# rapidshark-main-breakout-top-teensy-mk-1.net
KiCad netlist of a schematic drawn in EAGLE
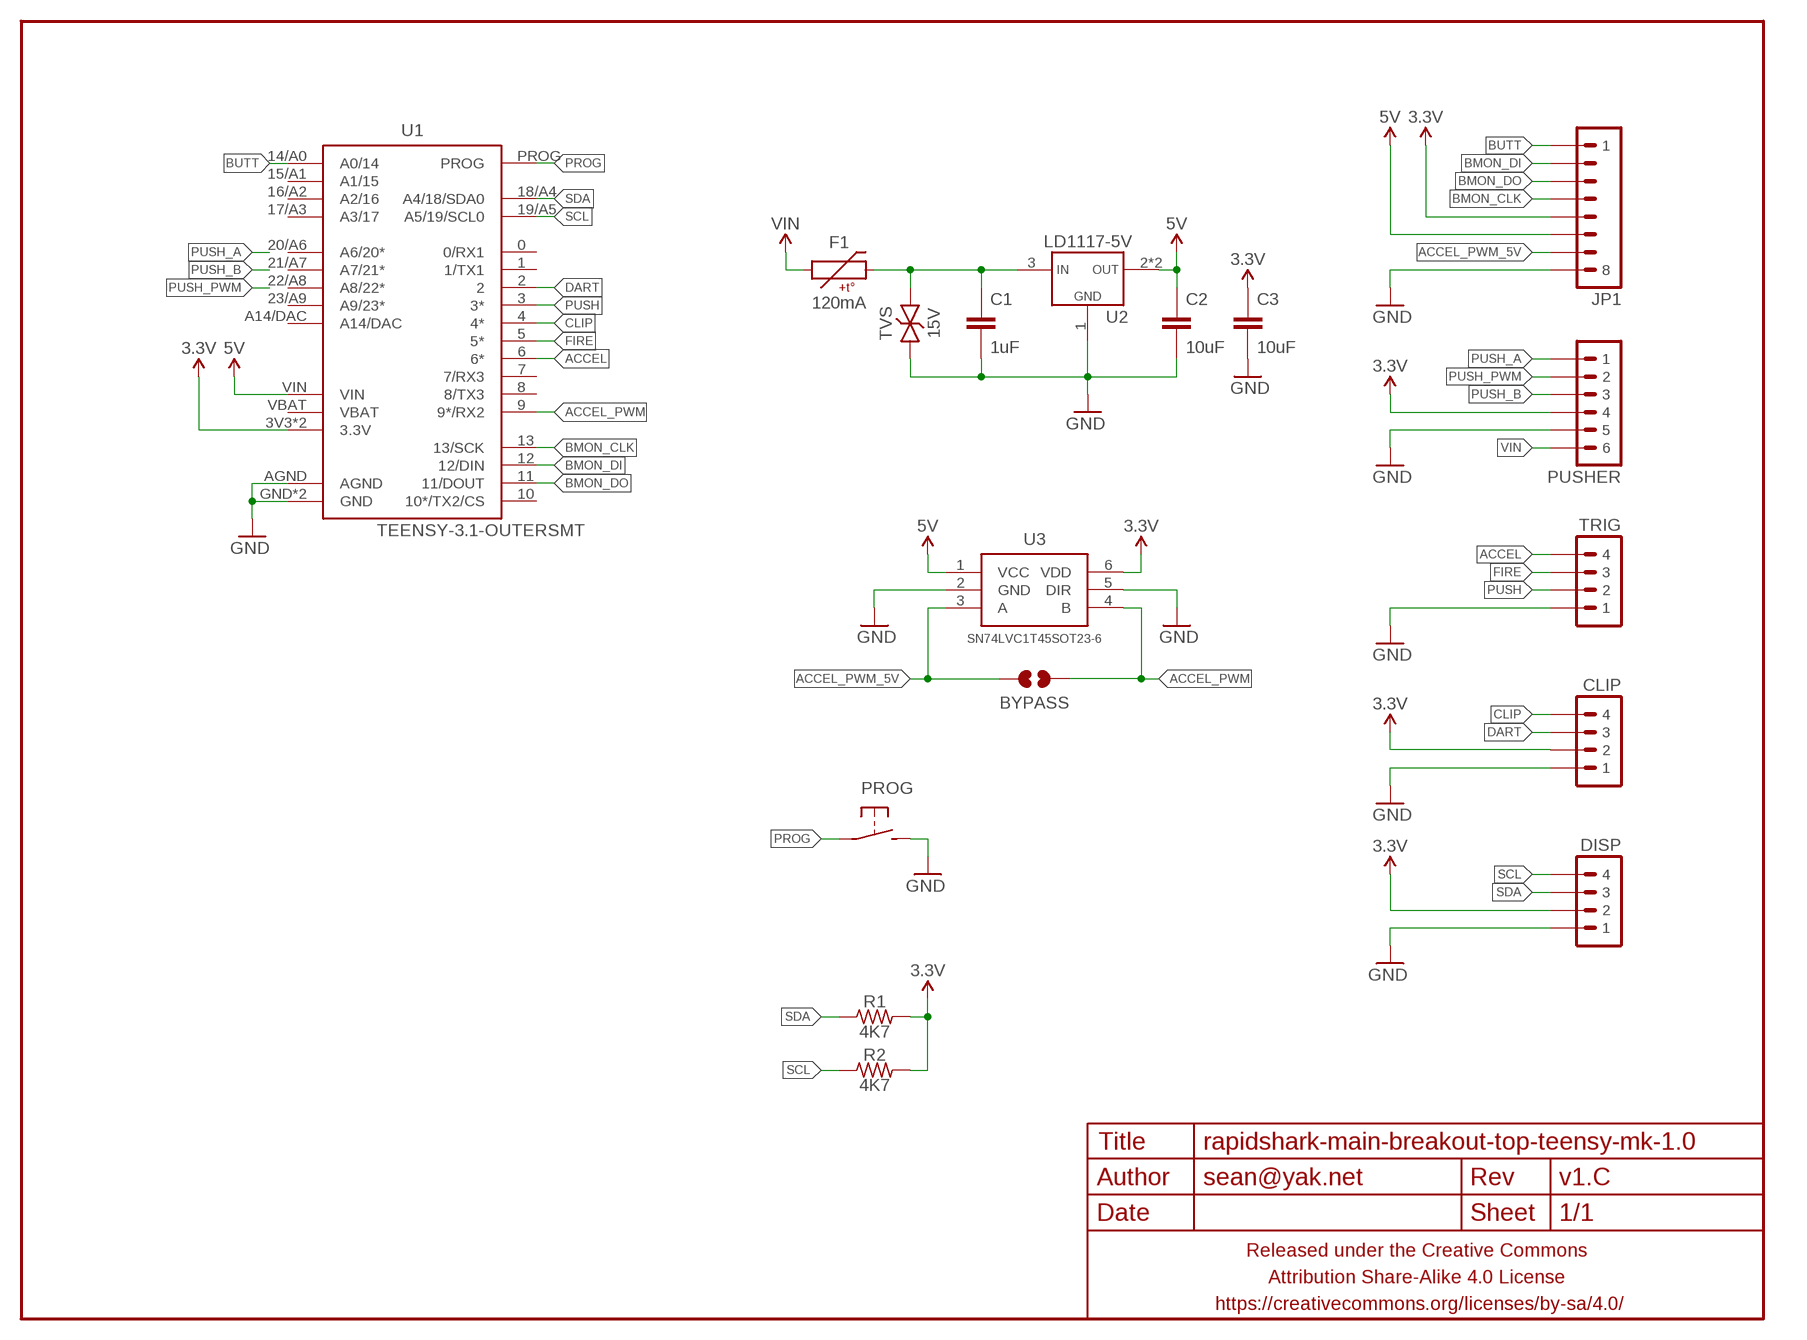
[diagram p0: schematic, sheet 1]

(export (version "E")
  (design (tool "Eeschema 10.0.6"))
  (components
    (comp (ref "BYPASS")
      (value "JUMPER-PAD-2-NOYES_SILK")
      (footprint "eagle-import:PAD-JUMPER-2-NO_YES_SILK")
      (libsource (lib "eagle-import") (part "JUMPER-PAD-2-NOYES_SILK"))
    )
    (comp (ref "C1")
      (value "1uF")
      (footprint "eagle-import:C0603")
      (libsource (lib "eagle-import") (part "CAPACITOR-CERAMICC0603"))
    )
    (comp (ref "C2")
      (value "10uF")
      (footprint "eagle-import:C0805")
      (libsource (lib "eagle-import") (part "CAPACITOR-CERAMICC0805"))
    )
    (comp (ref "C3")
      (value "10uF")
      (footprint "eagle-import:C0805")
      (libsource (lib "eagle-import") (part "CAPACITOR-CERAMICC0805"))
    )
    (comp (ref "CLIP")
      (value "M04JST-PTH-VERT")
      (footprint "eagle-import:JST-4-PH-VERT-PTH")
      (libsource (lib "eagle-import") (part "M04JST-PTH-VERT"))
    )
    (comp (ref "DISP")
      (value "M04JST-PTH-VERT")
      (footprint "eagle-import:JST-4-PH-VERT-PTH")
      (libsource (lib "eagle-import") (part "M04JST-PTH-VERT"))
    )
    (comp (ref "F1")
      (value "120mA")
      (footprint "eagle-import:PTC-1206")
      (libsource (lib "eagle-import") (part "PTCSMD"))
    )
    (comp (ref "FRAME1")
      (value "FRAME-LETTERNO_PACKAGE")
      (footprint "eagle-import:DUMMY")
      (fields (field (name "DESIGNER") "sean@yak.net") (field (name "VERSION") "v1.C"))
      (libsource (lib "eagle-import") (part "FRAME-LETTERNO_PACKAGE"))
    )
    (comp (ref "JP1")
      (value "M08SMD-RA-MALE-2MM")
      (footprint "eagle-import:1X08_SMD_RA_MALE_2MM")
      (libsource (lib "eagle-import") (part "M08SMD-RA-MALE-2MM"))
    )
    (comp (ref "PROG")
      (value "SPST-NO-TACTCK-PTS840-GK")
      (footprint "eagle-import:TACTILE-SMD-CK-PTS840-GK")
      (libsource (lib "eagle-import") (part "SPST-NO-TACTCK-PTS840-GK"))
    )
    (comp (ref "PUSHER")
      (value "M06JST-PH-PTH-VERT")
      (footprint "eagle-import:JST-6-PH-VERT-PTH")
      (libsource (lib "eagle-import") (part "M06JST-PH-PTH-VERT"))
    )
    (comp (ref "R1")
      (value "4K7")
      (footprint "eagle-import:R0603-TIGHTER")
      (libsource (lib "eagle-import") (part "RESISTORR0603-TIGHTER"))
    )
    (comp (ref "R2")
      (value "4K7")
      (footprint "eagle-import:R0603-TIGHTER")
      (libsource (lib "eagle-import") (part "RESISTORR0603-TIGHTER"))
    )
    (comp (ref "TRIG")
      (value "M04JST-PTH-VERT")
      (footprint "eagle-import:JST-4-PH-VERT-PTH")
      (libsource (lib "eagle-import") (part "M04JST-PTH-VERT"))
    )
    (comp (ref "TVS")
      (value "15V")
      (footprint "eagle-import:SMA-DIODE-TVS-BIDIR")
      (libsource (lib "eagle-import") (part "TVSSMA"))
    )
    (comp (ref "U1")
      (value "TEENSY-3.1-OUTERSMT")
      (footprint "eagle-import:TEENSY-3.1_SMT_BOTTOM_OUTERONLY")
      (libsource (lib "eagle-import") (part "TEENSY-3.1-OUTERSMT"))
    )
    (comp (ref "U2")
      (value "LD1117-5V")
      (footprint "eagle-import:SOT223")
      (libsource (lib "eagle-import") (part "VREG_1117SOT223"))
    )
    (comp (ref "U3")
      (value "SN74LVC1T45SOT23-6")
      (footprint "eagle-import:SOT23-6")
      (libsource (lib "eagle-import") (part "SN74LVC1T45SOT23-6"))
    )
  )
  (nets
    (net (code "1") (name "3.3V") (class "Default")
      (node (ref "C3") (pin "1") (pinfunction "1_1") (pintype "passive"))
      (node (ref "CLIP") (pin "2") (pinfunction "2_2") (pintype "passive"))
      (node (ref "DISP") (pin "2") (pinfunction "2_2") (pintype "passive"))
      (node (ref "JP1") (pin "5") (pinfunction "5_5") (pintype "passive"))
      (node (ref "PUSHER") (pin "4") (pinfunction "4_4") (pintype "passive"))
      (node (ref "R1") (pin "2") (pinfunction "2_2") (pintype "passive"))
      (node (ref "R2") (pin "2") (pinfunction "2_2") (pintype "passive"))
      (node (ref "U1") (pin "3V3") (pinfunction "3.3V_3V3") (pintype "bidirectional"))
      (node (ref "U1") (pin "3V3@1") (pinfunction "3.3V_3V3@1") (pintype "bidirectional"))
      (node (ref "U3") (pin "6") (pinfunction "VDD_6") (pintype "bidirectional"))
    )
    (net (code "2") (name "5V") (class "Default")
      (node (ref "C2") (pin "1") (pinfunction "1_1") (pintype "passive"))
      (node (ref "JP1") (pin "6") (pinfunction "6_6") (pintype "passive"))
      (node (ref "U1") (pin "VIN") (pinfunction "VIN_VIN") (pintype "bidirectional"))
      (node (ref "U2") (pin "2") (pinfunction "VOUT_2") (pintype "bidirectional"))
      (node (ref "U2") (pin "4") (pinfunction "VOUT_4") (pintype "bidirectional"))
      (node (ref "U3") (pin "1") (pinfunction "VCC_1") (pintype "bidirectional"))
    )
    (net (code "3") (name "ACCEL") (class "Default")
      (node (ref "TRIG") (pin "4") (pinfunction "4_4") (pintype "passive"))
      (node (ref "U1") (pin "6") (pinfunction "6*_6") (pintype "bidirectional"))
    )
    (net (code "4") (name "ACCEL_PWM") (class "Default")
      (node (ref "BYPASS") (pin "1") (pinfunction "1_1") (pintype "passive"))
      (node (ref "U1") (pin "9") (pinfunction "9*/RX2_9") (pintype "bidirectional"))
      (node (ref "U3") (pin "4") (pinfunction "B_4") (pintype "bidirectional"))
    )
    (net (code "5") (name "ACCEL_PWM_5V") (class "Default")
      (node (ref "BYPASS") (pin "2") (pinfunction "2_2") (pintype "passive"))
      (node (ref "JP1") (pin "7") (pinfunction "7_7") (pintype "passive"))
      (node (ref "U3") (pin "3") (pinfunction "A_3") (pintype "bidirectional"))
    )
    (net (code "6") (name "BMON_CLK") (class "Default")
      (node (ref "JP1") (pin "4") (pinfunction "4_4") (pintype "passive"))
      (node (ref "U1") (pin "13") (pinfunction "13/SCK_13") (pintype "bidirectional"))
    )
    (net (code "7") (name "BMON_DI") (class "Default")
      (node (ref "JP1") (pin "2") (pinfunction "2_2") (pintype "passive"))
      (node (ref "U1") (pin "12") (pinfunction "12/DIN_12") (pintype "bidirectional"))
    )
    (net (code "8") (name "BMON_DO") (class "Default")
      (node (ref "JP1") (pin "3") (pinfunction "3_3") (pintype "passive"))
      (node (ref "U1") (pin "11") (pinfunction "11/DOUT_11") (pintype "bidirectional"))
    )
    (net (code "9") (name "BUTT") (class "Default")
      (node (ref "JP1") (pin "1") (pinfunction "1_1") (pintype "passive"))
      (node (ref "U1") (pin "14/A0") (pinfunction "A0/14_14/A0") (pintype "bidirectional"))
    )
    (net (code "10") (name "CLIP") (class "Default")
      (node (ref "CLIP") (pin "4") (pinfunction "4_4") (pintype "passive"))
      (node (ref "U1") (pin "4") (pinfunction "4*_4") (pintype "bidirectional"))
    )
    (net (code "11") (name "DART") (class "Default")
      (node (ref "CLIP") (pin "3") (pinfunction "3_3") (pintype "passive"))
      (node (ref "U1") (pin "2") (pinfunction "2_2") (pintype "bidirectional"))
    )
    (net (code "12") (name "FIRE") (class "Default")
      (node (ref "TRIG") (pin "3") (pinfunction "3_3") (pintype "passive"))
      (node (ref "U1") (pin "5") (pinfunction "5*_5") (pintype "bidirectional"))
    )
    (net (code "13") (name "GND") (class "Default")
      (node (ref "C1") (pin "2") (pinfunction "2_2") (pintype "passive"))
      (node (ref "C2") (pin "2") (pinfunction "2_2") (pintype "passive"))
      (node (ref "C3") (pin "2") (pinfunction "2_2") (pintype "passive"))
      (node (ref "CLIP") (pin "1") (pinfunction "1_1") (pintype "passive"))
      (node (ref "DISP") (pin "1") (pinfunction "1_1") (pintype "passive"))
      (node (ref "JP1") (pin "8") (pinfunction "8_8") (pintype "passive"))
      (node (ref "PROG") (pin "3") (pinfunction "2_3") (pintype "passive"))
      (node (ref "PROG") (pin "4") (pinfunction "2_4") (pintype "passive"))
      (node (ref "PUSHER") (pin "5") (pinfunction "5_5") (pintype "passive"))
      (node (ref "TRIG") (pin "1") (pinfunction "1_1") (pintype "passive"))
      (node (ref "TVS") (pin "1") (pinfunction "1_1") (pintype "passive"))
      (node (ref "U1") (pin "AGND") (pinfunction "AGND_AGND") (pintype "bidirectional"))
      (node (ref "U1") (pin "GND") (pinfunction "GND_GND") (pintype "bidirectional"))
      (node (ref "U1") (pin "GND@1") (pinfunction "GND_GND@1") (pintype "bidirectional"))
      (node (ref "U2") (pin "1") (pinfunction "GND_1") (pintype "bidirectional"))
      (node (ref "U3") (pin "2") (pinfunction "GND_2") (pintype "bidirectional"))
      (node (ref "U3") (pin "5") (pinfunction "DIR_5") (pintype "bidirectional"))
    )
    (net (code "14") (name "Net-(U2-VIN)") (class "Default")
      (node (ref "C1") (pin "1") (pinfunction "1_1") (pintype "passive"))
      (node (ref "F1") (pin "2") (pinfunction "2_2") (pintype "passive"))
      (node (ref "TVS") (pin "2") (pinfunction "2_2") (pintype "passive"))
      (node (ref "U2") (pin "3") (pinfunction "VIN_3") (pintype "bidirectional"))
    )
    (net (code "15") (name "PROG") (class "Default")
      (node (ref "PROG") (pin "1") (pinfunction "1_1") (pintype "passive"))
      (node (ref "PROG") (pin "2") (pinfunction "1_2") (pintype "passive"))
      (node (ref "U1") (pin "PROG") (pinfunction "PROG_PROG") (pintype "bidirectional"))
    )
    (net (code "16") (name "PUSH") (class "Default")
      (node (ref "TRIG") (pin "2") (pinfunction "2_2") (pintype "passive"))
      (node (ref "U1") (pin "3") (pinfunction "3*_3") (pintype "bidirectional"))
    )
    (net (code "17") (name "PUSH_A") (class "Default")
      (node (ref "PUSHER") (pin "1") (pinfunction "1_1") (pintype "passive"))
    )
    (net (code "18") (name "PUSH_B") (class "Default")
      (node (ref "PUSHER") (pin "3") (pinfunction "3_3") (pintype "passive"))
    )
    (net (code "19") (name "PUSH_PWM") (class "Default")
      (node (ref "PUSHER") (pin "2") (pinfunction "2_2") (pintype "passive"))
    )
    (net (code "20") (name "SCL") (class "Default")
      (node (ref "DISP") (pin "4") (pinfunction "4_4") (pintype "passive"))
      (node (ref "R2") (pin "1") (pinfunction "1_1") (pintype "passive"))
      (node (ref "U1") (pin "19/A5") (pinfunction "A5/19/SCL0_19/A5") (pintype "bidirectional"))
    )
    (net (code "21") (name "SDA") (class "Default")
      (node (ref "DISP") (pin "3") (pinfunction "3_3") (pintype "passive"))
      (node (ref "R1") (pin "1") (pinfunction "1_1") (pintype "passive"))
      (node (ref "U1") (pin "18/A4") (pinfunction "A4/18/SDA0_18/A4") (pintype "bidirectional"))
    )
    (net (code "22") (name "VIN") (class "Default")
      (node (ref "F1") (pin "1") (pinfunction "1_1") (pintype "passive"))
      (node (ref "PUSHER") (pin "6") (pinfunction "6_6") (pintype "passive"))
    )
    (net (code "23") (name "unconnected-(U1-0{slash}RX1-Pad0)") (class "Default")
      (node (ref "U1") (pin "0") (pinfunction "0/RX1_0") (pintype "bidirectional"))
    )
    (net (code "24") (name "unconnected-(U1-1{slash}TX1-Pad1)") (class "Default")
      (node (ref "U1") (pin "1") (pinfunction "1/TX1_1") (pintype "bidirectional"))
    )
    (net (code "25") (name "unconnected-(U1-7{slash}RX3-Pad7)") (class "Default")
      (node (ref "U1") (pin "7") (pinfunction "7/RX3_7") (pintype "bidirectional"))
    )
    (net (code "26") (name "unconnected-(U1-8{slash}TX3-Pad8)") (class "Default")
      (node (ref "U1") (pin "8") (pinfunction "8/TX3_8") (pintype "bidirectional"))
    )
    (net (code "27") (name "unconnected-(U1-10*{slash}TX2{slash}CS-Pad10)") (class "Default")
      (node (ref "U1") (pin "10") (pinfunction "10*/TX2/CS_10") (pintype "bidirectional"))
    )
    (net (code "28") (name "unconnected-(U1-A1{slash}15-Pad15{slash}A1)") (class "Default")
      (node (ref "U1") (pin "15/A1") (pinfunction "A1/15_15/A1") (pintype "bidirectional"))
    )
    (net (code "29") (name "unconnected-(U1-A2{slash}16-Pad16{slash}A2)") (class "Default")
      (node (ref "U1") (pin "16/A2") (pinfunction "A2/16_16/A2") (pintype "bidirectional"))
    )
    (net (code "30") (name "unconnected-(U1-A3{slash}17-Pad17{slash}A3)") (class "Default")
      (node (ref "U1") (pin "17/A3") (pinfunction "A3/17_17/A3") (pintype "bidirectional"))
    )
    (net (code "31") (name "unconnected-(U1-A6{slash}20*-Pad20{slash}A6)") (class "Default")
      (node (ref "U1") (pin "20/A6") (pinfunction "A6/20*_20/A6") (pintype "bidirectional"))
    )
    (net (code "32") (name "unconnected-(U1-A7{slash}21*-Pad21{slash}A7)") (class "Default")
      (node (ref "U1") (pin "21/A7") (pinfunction "A7/21*_21/A7") (pintype "bidirectional"))
    )
    (net (code "33") (name "unconnected-(U1-A8{slash}22*-Pad22{slash}A8)") (class "Default")
      (node (ref "U1") (pin "22/A8") (pinfunction "A8/22*_22/A8") (pintype "bidirectional"))
    )
    (net (code "34") (name "unconnected-(U1-A9{slash}23*-Pad23{slash}A9)") (class "Default")
      (node (ref "U1") (pin "23/A9") (pinfunction "A9/23*_23/A9") (pintype "bidirectional"))
    )
    (net (code "35") (name "unconnected-(U1-PadA14{slash}DAC)") (class "Default")
      (node (ref "U1") (pin "A14/DAC") (pinfunction "A14/DAC_A14/DAC") (pintype "bidirectional"))
    )
    (net (code "36") (name "unconnected-(U1-PadVBAT)") (class "Default")
      (node (ref "U1") (pin "VBAT") (pinfunction "VBAT_VBAT") (pintype "bidirectional"))
    )
  )
)
